# DM1092_Power_Supply.net
KiCad netlist of a schematic drawn in Altium Designer
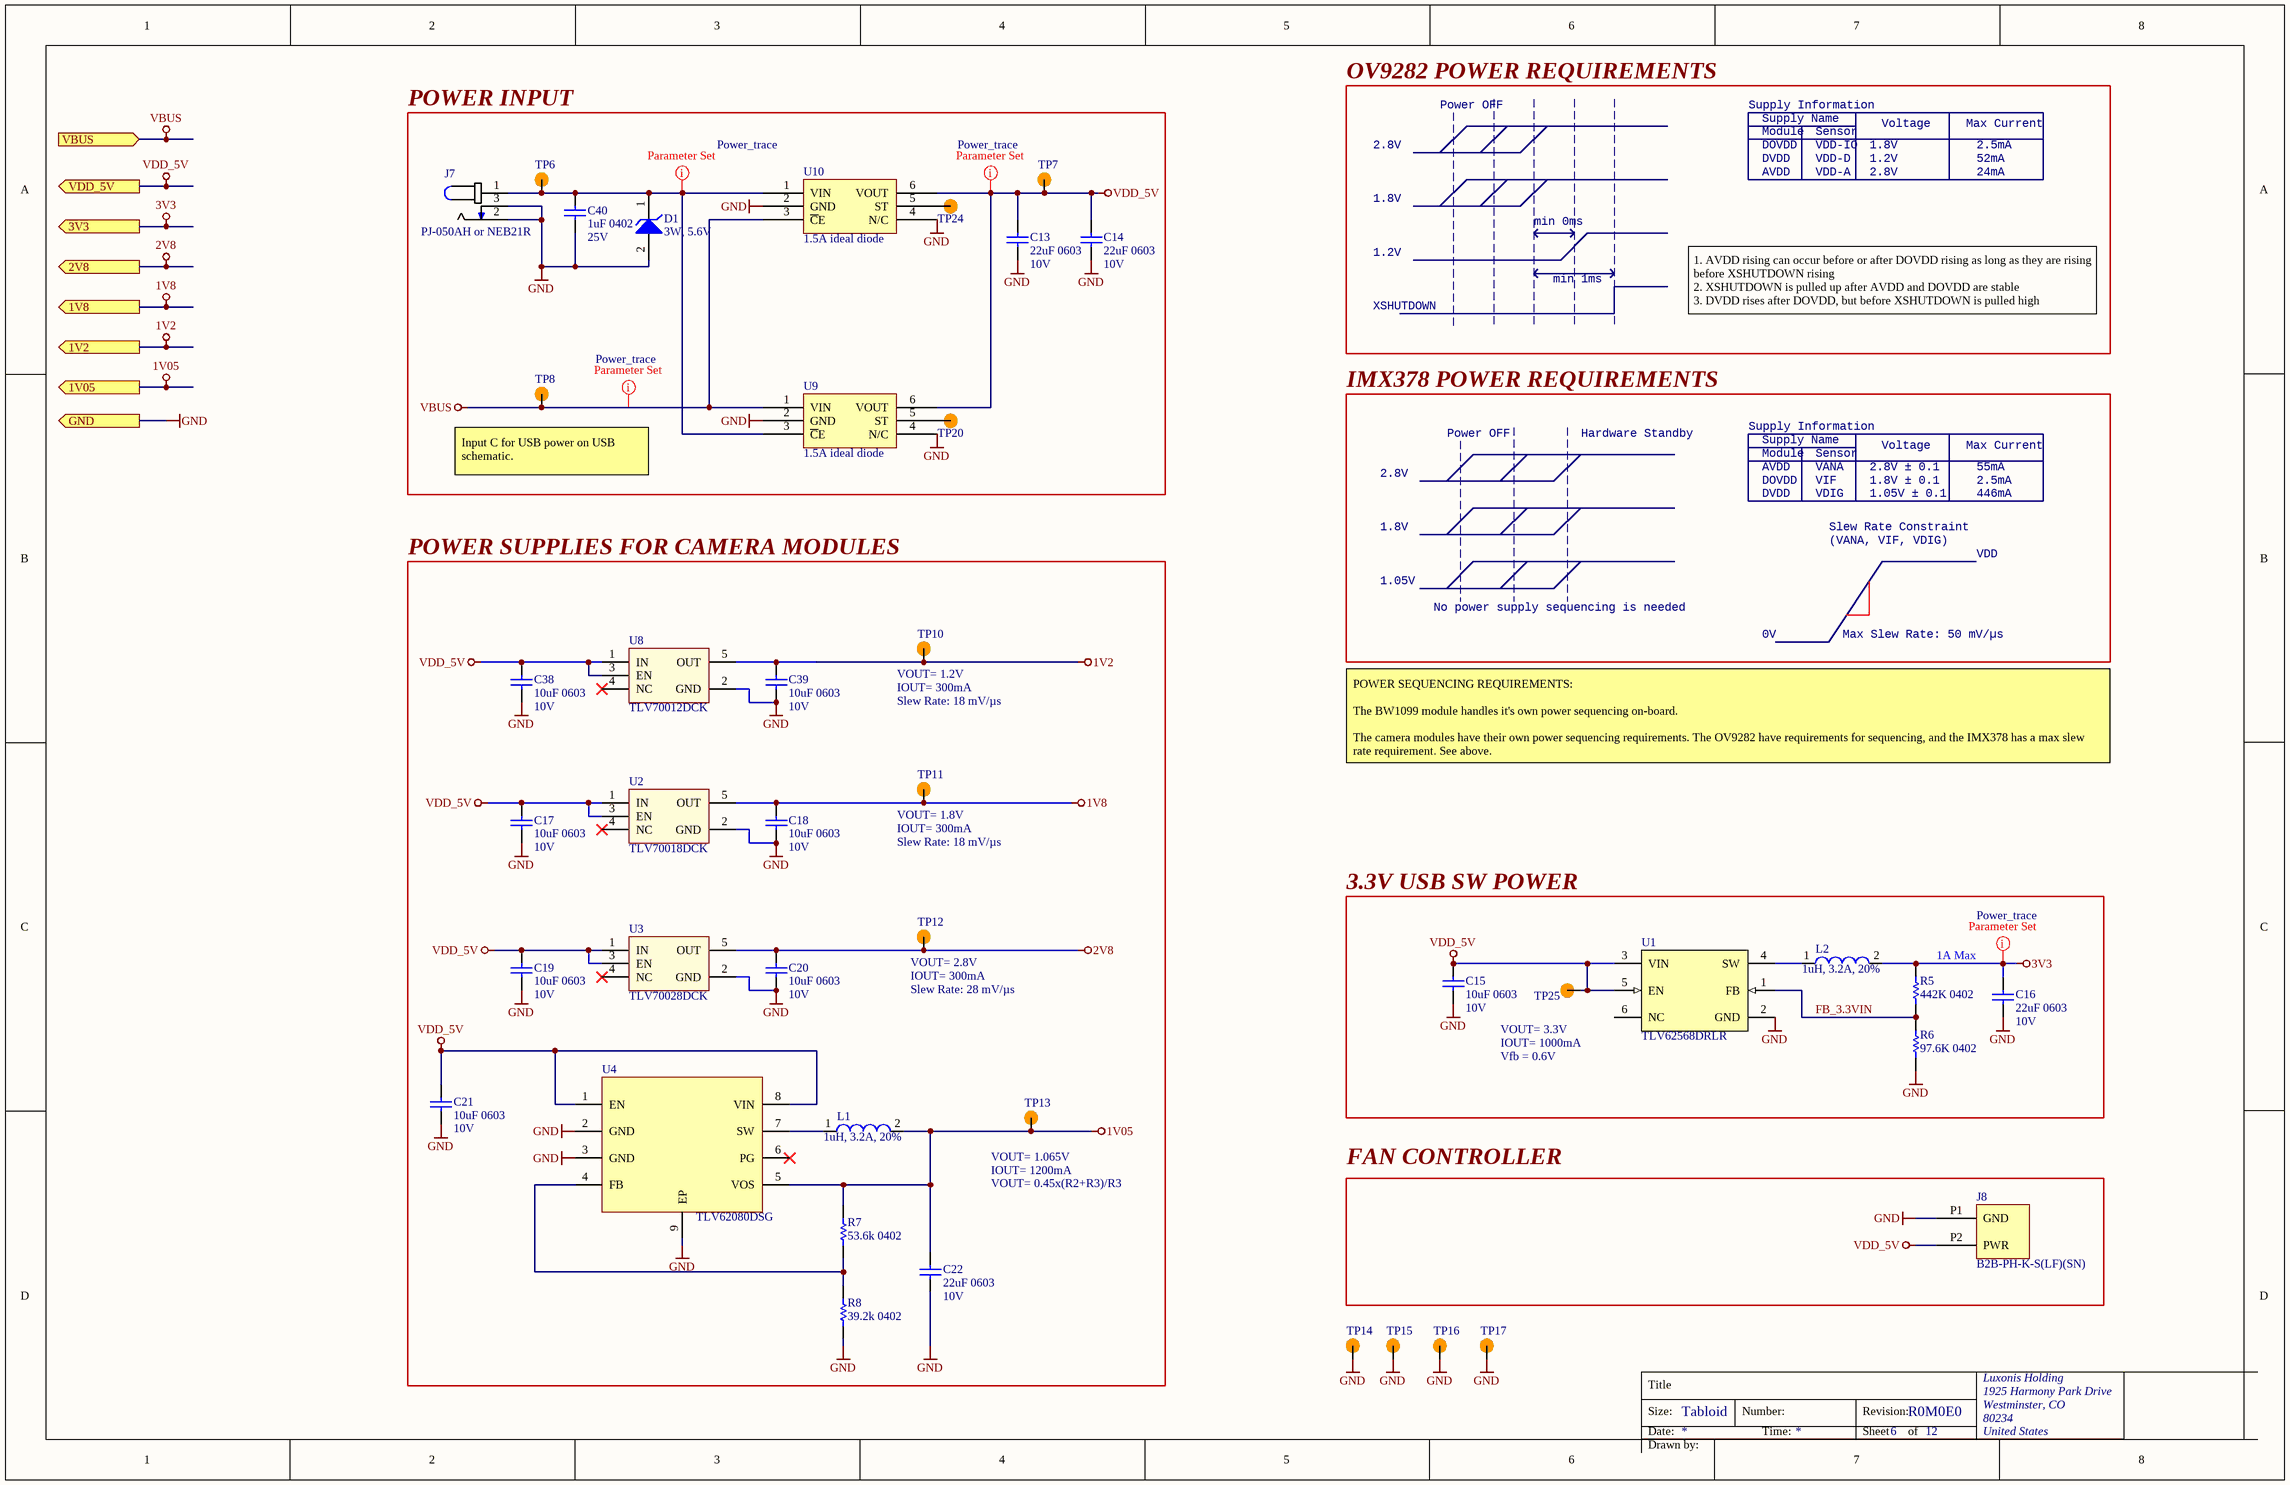
[diagram p0: DM1092_Power_Supply.SchDoc]

(export (version "E")
  (design (tool "Eeschema 10.0.6"))
  (components
    (comp (ref "C13")
      (value "22uF 0603")
      (footprint "CAP_Altium_Vault_Generic:CAPC0603(1608)100_L")
      (description "CAP CER 22UF 10V X5R 0603 20%")
      (fields (field (name "TOLERANCE") "20%") (field (name "VOLTAGE RATING") "10V"))
      (libsource (lib "LuxonisMaster") (part "GRM188R61A226ME15D"))
    )
    (comp (ref "C14")
      (value "22uF 0603")
      (footprint "CAP_Altium_Vault_Generic:CAPC0603(1608)100_L")
      (description "CAP CER 22UF 10V X5R 0603 20%")
      (fields (field (name "TOLERANCE") "20%") (field (name "VOLTAGE RATING") "10V"))
      (libsource (lib "LuxonisMaster") (part "GRM188R61A226ME15D"))
    )
    (comp (ref "C15")
      (value "10uF 0603")
      (footprint "CAP_Altium_Vault_Generic:CAPC0603(1608)100_L")
      (description "CAP CER 10UF 10V X5R 0603 20%")
      (fields (field (name "TOLERANCE") "20%") (field (name "VOLTAGE RATING") "10V"))
      (libsource (lib "LuxonisMaster") (part "GRM188R61A106ME69D"))
    )
    (comp (ref "C16")
      (value "22uF 0603")
      (footprint "CAP_Altium_Vault_Generic:CAPC0603(1608)100_N")
      (description "CAP CER 22UF 10V X5R 0603 20%")
      (fields (field (name "TOLERANCE") "20%") (field (name "VOLTAGE RATING") "10V"))
      (libsource (lib "LuxonisMaster") (part "GRM188R61A226ME15D"))
    )
    (comp (ref "C17")
      (value "10uF 0603")
      (footprint "CAP_Altium_Vault_Generic:CAPC0603(1608)100_L")
      (description "CAP CER 10UF 10V X5R 0603 20%")
      (fields (field (name "TOLERANCE") "20%") (field (name "VOLTAGE RATING") "10V"))
      (libsource (lib "LuxonisMaster") (part "GRM188R61A106ME69D"))
    )
    (comp (ref "C18")
      (value "10uF 0603")
      (footprint "CAP_Altium_Vault_Generic:CAPC0603(1608)100_L")
      (description "CAP CER 10UF 10V X5R 0603 20%")
      (fields (field (name "TOLERANCE") "20%") (field (name "VOLTAGE RATING") "10V"))
      (libsource (lib "LuxonisMaster") (part "GRM188R61A106ME69D"))
    )
    (comp (ref "C19")
      (value "10uF 0603")
      (footprint "CAP_Altium_Vault_Generic:CAPC0603(1608)100_L")
      (description "CAP CER 10UF 10V X5R 0603 20%")
      (fields (field (name "TOLERANCE") "20%") (field (name "VOLTAGE RATING") "10V"))
      (libsource (lib "LuxonisMaster") (part "GRM188R61A106ME69D"))
    )
    (comp (ref "C20")
      (value "10uF 0603")
      (footprint "CAP_Altium_Vault_Generic:CAPC0603(1608)100_L")
      (description "CAP CER 10UF 10V X5R 0603 20%")
      (fields (field (name "TOLERANCE") "20%") (field (name "VOLTAGE RATING") "10V"))
      (libsource (lib "LuxonisMaster") (part "GRM188R61A106ME69D"))
    )
    (comp (ref "C21")
      (value "10uF 0603")
      (footprint "CAP_Altium_Vault_Generic:CAPC0603(1608)100_L")
      (description "CAP CER 10UF 10V X5R 0603 20%")
      (fields (field (name "TOLERANCE") "20%") (field (name "VOLTAGE RATING") "10V"))
      (libsource (lib "LuxonisMaster") (part "GRM188R61A106ME69D"))
    )
    (comp (ref "C22")
      (value "22uF 0603")
      (footprint "CAP_Altium_Vault_Generic:CAPC0603(1608)100_L")
      (description "CAP CER 22UF 10V X5R 0603 20%")
      (fields (field (name "TOLERANCE") "20%") (field (name "VOLTAGE RATING") "10V"))
      (libsource (lib "LuxonisMaster") (part "GRM188R61A226ME15D"))
    )
    (comp (ref "C38")
      (value "10uF 0603")
      (footprint "CAP_Altium_Vault_Generic:CAPC0603(1608)100_L")
      (description "CAP CER 10UF 10V X5R 0603 20%")
      (fields (field (name "TOLERANCE") "20%") (field (name "VOLTAGE RATING") "10V"))
      (libsource (lib "LuxonisMaster") (part "GRM188R61A106ME69D"))
    )
    (comp (ref "C39")
      (value "10uF 0603")
      (footprint "CAP_Altium_Vault_Generic:CAPC0603(1608)100_L")
      (description "CAP CER 10UF 10V X5R 0603 20%")
      (fields (field (name "TOLERANCE") "20%") (field (name "VOLTAGE RATING") "10V"))
      (libsource (lib "LuxonisMaster") (part "GRM188R61A106ME69D"))
    )
    (comp (ref "C40")
      (value "1uF 0402")
      (footprint "CAP_Altium_Vault_Generic:CAPC0402(1005)70_L")
      (description "CAP CER 1UF 25V X5R 0402 10%")
      (fields
        (field (name "TOLERANCE") "10%")
        (field (name "VOLTAGE") "25V")
        (field (name "VOLTAGE RATING") "25V")
      )
      (libsource (lib "LuxonisMaster") (part "GRM155R61E105KA12D"))
    )
    (comp (ref "D1")
      (value "3W, 5.6V")
      (footprint "DM1092_R0M0E0:1SMB5919BT3G")
      (description "DIODE ZENER 5.6V 3W SMB")
      (fields (field (name "TOLERANCE") "5%"))
      (libsource (lib "DM1092_R0M0E0") (part "1SMB5919BT3G"))
    )
    (comp (ref "J7")
      (value "PJ-050AH or NEB21R")
      (footprint "LuxonisMaster:PJ-050AH/NEB21R_COMBO")
      (description "CONN POWER PIN 2 POS RA PTH Barrel jack 2.1mm x 5.5mm combo footprint")
      (libsource (lib "LuxonisMaster") (part "PJ-050AH/NEB21R_COMBO"))
    )
    (comp (ref "J8")
      (value "B2B-PH-K-S(LF)(SN)")
      (footprint "LuxonisMaster:B2B-PH-K-S(LF)(SN)")
      (description "CONN HEADER VERT 2POS 2MM")
      (fields (field (name "MANUFACTURER") "JST"))
      (libsource (lib "LuxonisMaster") (part "B2B-PH-K-S(LF)(SN)"))
    )
    (comp (ref "L1")
      (value "1uH, 3.2A, 20%")
      (footprint "LuxonisMaster:DFE252012P-1R0M=P2")
      (description "FIXED IND 1UH 3.2A 42 MOHM SMD")
      (fields
        (field (name "MANUFACTURER") "Murata")
        (field (name "MANUFACTURER PART NUMBER") "DFE252012P-1R0M=P2")
      )
      (libsource (lib "LuxonisMaster") (part "DFE252012P-1R0M=P2"))
    )
    (comp (ref "L2")
      (value "1uH, 3.2A, 20%")
      (footprint "LuxonisMaster:DFE252012P-1R0M=P2")
      (description "FIXED IND 1UH 3.2A 42 MOHM SMD")
      (fields
        (field (name "MANUFACTURER") "Murata")
        (field (name "MANUFACTURER PART NUMBER") "DFE252012P-1R0M=P2")
      )
      (libsource (lib "LuxonisMaster") (part "DFE252012P-1R0M=P2"))
    )
    (comp (ref "R5")
      (value "442K 0402")
      (footprint "RES_Altium_Vault_Generic:RESC0402(1005)_N")
      (description "RES SMD 442K OHM 1% 1/16W 0402")
      (fields (field (name "TOLERANCE") "1%"))
      (libsource (lib "DM1092_R0M0E0") (part "CRCW0402442KFKED"))
    )
    (comp (ref "R6")
      (value "97.6K 0402")
      (footprint "RES_Altium_Vault_Generic:RESC0402(1005)_N")
      (description "RES SMD 97.6K OHM 1% 1/16W 0402")
      (fields (field (name "TOLERANCE") "1%"))
      (libsource (lib "DM1092_R0M0E0") (part "CRCW040297K6FKED"))
    )
    (comp (ref "R7")
      (value "53.6k 0402")
      (footprint "RES_Altium_Vault_Generic:RESC0402(1005)_L")
      (description "RES SMD 53.6K OHM 1% 1/16W 0402")
      (fields (field (name "TOLERANCE") "1%"))
      (libsource (lib "LuxonisMaster") (part "CRCW040253K6FKED"))
    )
    (comp (ref "R8")
      (value "39.2k 0402")
      (footprint "RES_Altium_Vault_Generic:RESC0402(1005)_L")
      (description "RES SMD 39.2K OHM 1% 1/16W 0402")
      (fields (field (name "TOLERANCE") "1%"))
      (libsource (lib "LuxonisMaster") (part "CRCW040239K2FKED"))
    )
    (comp (ref "TP6")
      (value "TP100_200_NS")
      (footprint "LuxonisMaster:TP100_200_NS")
      (libsource (lib "LuxonisMaster") (part "TEST_POINT"))
    )
    (comp (ref "TP7")
      (value "TP100_200_NS")
      (footprint "LuxonisMaster:TP100_200_NS")
      (libsource (lib "LuxonisMaster") (part "TEST_POINT"))
    )
    (comp (ref "TP8")
      (value "TP100_200_NS")
      (footprint "LuxonisMaster:TP100_200_NS")
      (libsource (lib "LuxonisMaster") (part "TEST_POINT"))
    )
    (comp (ref "TP10")
      (value "TP100_200_NS")
      (footprint "LuxonisMaster:TP100_200_NS")
      (libsource (lib "LuxonisMaster") (part "TEST_POINT"))
    )
    (comp (ref "TP11")
      (value "TP100_200_NS")
      (footprint "LuxonisMaster:TP100_200_NS")
      (libsource (lib "LuxonisMaster") (part "TEST_POINT"))
    )
    (comp (ref "TP12")
      (value "TP100_200_NS")
      (footprint "LuxonisMaster:TP100_200_NS")
      (libsource (lib "LuxonisMaster") (part "TEST_POINT"))
    )
    (comp (ref "TP13")
      (value "TP100_200_NS")
      (footprint "LuxonisMaster:TP100_200_NS")
      (libsource (lib "LuxonisMaster") (part "TEST_POINT"))
    )
    (comp (ref "TP14")
      (value "TP100_200_NS")
      (footprint "LuxonisMaster:TP100_200_NS")
      (libsource (lib "LuxonisMaster") (part "TEST_POINT"))
    )
    (comp (ref "TP15")
      (value "TP100_200_NS")
      (footprint "LuxonisMaster:TP100_200_NS")
      (libsource (lib "LuxonisMaster") (part "TEST_POINT"))
    )
    (comp (ref "TP16")
      (value "TP100_200_NS")
      (footprint "LuxonisMaster:TP100_200_NS")
      (libsource (lib "LuxonisMaster") (part "TEST_POINT"))
    )
    (comp (ref "TP17")
      (value "TP100_200_NS")
      (footprint "LuxonisMaster:TP100_200_NS")
      (libsource (lib "LuxonisMaster") (part "TEST_POINT"))
    )
    (comp (ref "TP20")
      (value "TP100_200_NS")
      (footprint "LuxonisMaster:TP100_200_NS")
      (libsource (lib "LuxonisMaster") (part "TEST_POINT"))
    )
    (comp (ref "TP24")
      (value "TP100_200_NS")
      (footprint "LuxonisMaster:TP100_200_NS")
      (libsource (lib "LuxonisMaster") (part "TEST_POINT"))
    )
    (comp (ref "TP25")
      (value "TP100_200_NS")
      (footprint "LuxonisMaster:TP100_200_NS")
      (libsource (lib "LuxonisMaster") (part "TEST_POINT"))
    )
    (comp (ref "U1")
      (value "TLV62568DRLR")
      (footprint "BW1092_R0M0E0:TLV62568DRLR")
      (description "IC REG BUCK ADJ 1A SOT563-6")
      (libsource (lib "DM1092_R0M0E0") (part "TLV62568DRLR"))
    )
    (comp (ref "U2")
      (value "TLV70018DCK")
      (footprint "LuxonisMaster:TLV70018DCK")
      (description "IC REG LINEAR 1.8V 200MA SC70-5 Linear Voltage Regulator IC  1 Output  200mA SC-70-5")
      (libsource (lib "LuxonisMaster") (part "TLV70018DCK"))
    )
    (comp (ref "U3")
      (value "TLV70028DCK")
      (footprint "LuxonisMaster:TLV70028DCK")
      (description "IC REG LINEAR 2.8V 200MA SC70-5 Linear Voltage Regulator IC  1 Output  200mA SC-70-5")
      (libsource (lib "LuxonisMaster") (part "TLV70028DCK"))
    )
    (comp (ref "U4")
      (value "TLV62080DSG")
      (footprint "LuxonisMaster:TLV62080DSG")
      (description "IC REG BUCK ADJ 1.2A SYNC 8WSON")
      (libsource (lib "LuxonisMaster") (part "TLV62080DSG"))
    )
    (comp (ref "U8")
      (value "TLV70012DCK")
      (footprint "LuxonisMaster:TLV70012DCK")
      (description "IC REG LINEAR 1.2V 200MA SC70-5")
      (libsource (lib "LuxonisMaster") (part "TLV70012DCK"))
    )
    (comp (ref "U9")
      (value "1.5A ideal diode")
      (footprint "BW1098OBC_R2M0E2:LM66100DCKR")
      (description "IC OR CTRLR IDEAL DIODE SC70-6")
      (libsource (lib "BW1098OBC_R2M0E2") (part "LM66100DCKR"))
    )
    (comp (ref "U10")
      (value "1.5A ideal diode")
      (footprint "BW1098OBC_R2M0E2:LM66100DCKR")
      (description "IC OR CTRLR IDEAL DIODE SC70-6")
      (libsource (lib "BW1098OBC_R2M0E2") (part "LM66100DCKR"))
    )
  )
  (nets
    (net (code "1") (name "/FB_3.3VIN") (class "Default")
      (node (ref "R5") (pin "1") (pinfunction "1_1") (pintype "passive"))
      (node (ref "R6") (pin "2") (pinfunction "2_2") (pintype "passive"))
      (node (ref "U1") (pin "1") (pinfunction "FB_1") (pintype "input"))
    )
    (net (code "2") (name "1V2") (class "Default")
      (node (ref "C39") (pin "2") (pinfunction "2_2") (pintype "passive"))
      (node (ref "TP10") (pin "1") (pintype "passive"))
      (node (ref "U8") (pin "5") (pinfunction "OUT_5") (pintype "passive"))
    )
    (net (code "3") (name "1V05") (class "Default")
      (node (ref "C22") (pin "2") (pinfunction "2_2") (pintype "passive"))
      (node (ref "L1") (pin "2") (pinfunction "2_2") (pintype "passive"))
      (node (ref "R7") (pin "2") (pinfunction "2_2") (pintype "passive"))
      (node (ref "TP13") (pin "1") (pintype "passive"))
      (node (ref "U4") (pin "5") (pinfunction "VOS_5") (pintype "passive"))
    )
    (net (code "4") (name "1V8") (class "Default")
      (node (ref "C18") (pin "2") (pinfunction "2_2") (pintype "passive"))
      (node (ref "TP11") (pin "1") (pintype "passive"))
      (node (ref "U2") (pin "5") (pinfunction "OUT_5") (pintype "passive"))
    )
    (net (code "5") (name "2V8") (class "Default")
      (node (ref "C20") (pin "2") (pinfunction "2_2") (pintype "passive"))
      (node (ref "TP12") (pin "1") (pintype "passive"))
      (node (ref "U3") (pin "5") (pinfunction "OUT_5") (pintype "passive"))
    )
    (net (code "6") (name "3V3") (class "Default")
      (node (ref "C16") (pin "1") (pinfunction "1_1") (pintype "passive"))
      (node (ref "L2") (pin "2") (pinfunction "2_2") (pintype "passive"))
      (node (ref "R5") (pin "2") (pinfunction "2_2") (pintype "passive"))
    )
    (net (code "7") (name "GND") (class "Default")
      (node (ref "C13") (pin "1") (pinfunction "1_1") (pintype "passive"))
      (node (ref "C14") (pin "1") (pinfunction "1_1") (pintype "passive"))
      (node (ref "C15") (pin "1") (pinfunction "1_1") (pintype "passive"))
      (node (ref "C16") (pin "2") (pinfunction "2_2") (pintype "passive"))
      (node (ref "C17") (pin "1") (pinfunction "1_1") (pintype "passive"))
      (node (ref "C18") (pin "1") (pinfunction "1_1") (pintype "passive"))
      (node (ref "C19") (pin "1") (pinfunction "1_1") (pintype "passive"))
      (node (ref "C20") (pin "1") (pinfunction "1_1") (pintype "passive"))
      (node (ref "C21") (pin "1") (pinfunction "1_1") (pintype "passive"))
      (node (ref "C22") (pin "1") (pinfunction "1_1") (pintype "passive"))
      (node (ref "C38") (pin "1") (pinfunction "1_1") (pintype "passive"))
      (node (ref "C39") (pin "1") (pinfunction "1_1") (pintype "passive"))
      (node (ref "C40") (pin "1") (pinfunction "1_1") (pintype "passive"))
      (node (ref "D1") (pin "2") (pinfunction "A_2") (pintype "passive"))
      (node (ref "J7") (pin "2") (pinfunction "2_2") (pintype "passive"))
      (node (ref "J7") (pin "3") (pinfunction "3_3") (pintype "passive"))
      (node (ref "J8") (pin "P1") (pinfunction "GND_P1") (pintype "passive"))
      (node (ref "R6") (pin "1") (pinfunction "1_1") (pintype "passive"))
      (node (ref "R8") (pin "1") (pinfunction "1_1") (pintype "passive"))
      (node (ref "TP14") (pin "1") (pintype "passive"))
      (node (ref "TP15") (pin "1") (pintype "passive"))
      (node (ref "TP16") (pin "1") (pintype "passive"))
      (node (ref "TP17") (pin "1") (pintype "passive"))
      (node (ref "U1") (pin "2") (pinfunction "GND_2") (pintype "power_in"))
      (node (ref "U10") (pin "2") (pinfunction "GND_2") (pintype "passive"))
      (node (ref "U10") (pin "4") (pinfunction "N/C_4") (pintype "passive"))
      (node (ref "U2") (pin "2") (pinfunction "GND_2") (pintype "passive"))
      (node (ref "U3") (pin "2") (pinfunction "GND_2") (pintype "passive"))
      (node (ref "U4") (pin "2") (pinfunction "GND_2") (pintype "passive"))
      (node (ref "U4") (pin "3") (pinfunction "GND_3") (pintype "passive"))
      (node (ref "U4") (pin "9") (pinfunction "EP_9") (pintype "passive"))
      (node (ref "U8") (pin "2") (pinfunction "GND_2") (pintype "passive"))
      (node (ref "U9") (pin "2") (pinfunction "GND_2") (pintype "passive"))
      (node (ref "U9") (pin "4") (pinfunction "N/C_4") (pintype "passive"))
    )
    (net (code "8") (name "Net-(D1-K)") (class "Default")
      (node (ref "C40") (pin "2") (pinfunction "2_2") (pintype "passive"))
      (node (ref "D1") (pin "1") (pinfunction "K_1") (pintype "passive"))
      (node (ref "J7") (pin "1") (pinfunction "1_1") (pintype "passive"))
      (node (ref "TP6") (pin "1") (pintype "passive"))
      (node (ref "U10") (pin "1") (pinfunction "VIN_1") (pintype "passive"))
      (node (ref "U9") (pin "3") (pinfunction "~{C}E_3") (pintype "passive"))
    )
    (net (code "9") (name "Net-(U1-SW)") (class "Default")
      (node (ref "L2") (pin "1") (pinfunction "1_1") (pintype "passive"))
      (node (ref "U1") (pin "4") (pinfunction "SW_4") (pintype "power_in"))
    )
    (net (code "10") (name "Net-(U4-FB)") (class "Default")
      (node (ref "R7") (pin "1") (pinfunction "1_1") (pintype "passive"))
      (node (ref "R8") (pin "2") (pinfunction "2_2") (pintype "passive"))
      (node (ref "U4") (pin "4") (pinfunction "FB_4") (pintype "passive"))
    )
    (net (code "11") (name "Net-(U4-SW)") (class "Default")
      (node (ref "L1") (pin "1") (pinfunction "1_1") (pintype "passive"))
      (node (ref "U4") (pin "7") (pinfunction "SW_7") (pintype "passive"))
    )
    (net (code "12") (name "Net-(U9-ST)") (class "Default")
      (node (ref "TP20") (pin "1") (pintype "passive"))
      (node (ref "U9") (pin "5") (pinfunction "ST_5") (pintype "passive"))
    )
    (net (code "13") (name "Net-(U10-ST)") (class "Default")
      (node (ref "TP24") (pin "1") (pintype "passive"))
      (node (ref "U10") (pin "5") (pinfunction "ST_5") (pintype "passive"))
    )
    (net (code "14") (name "VBUS") (class "Default")
      (node (ref "TP8") (pin "1") (pintype "passive"))
      (node (ref "U10") (pin "3") (pinfunction "~{C}E_3") (pintype "passive"))
      (node (ref "U9") (pin "1") (pinfunction "VIN_1") (pintype "passive"))
    )
    (net (code "15") (name "VDD_5V") (class "Default")
      (node (ref "C13") (pin "2") (pinfunction "2_2") (pintype "passive"))
      (node (ref "C14") (pin "2") (pinfunction "2_2") (pintype "passive"))
      (node (ref "C15") (pin "2") (pinfunction "2_2") (pintype "passive"))
      (node (ref "C17") (pin "2") (pinfunction "2_2") (pintype "passive"))
      (node (ref "C19") (pin "2") (pinfunction "2_2") (pintype "passive"))
      (node (ref "C21") (pin "2") (pinfunction "2_2") (pintype "passive"))
      (node (ref "C38") (pin "2") (pinfunction "2_2") (pintype "passive"))
      (node (ref "J8") (pin "P2") (pinfunction "PWR_P2") (pintype "passive"))
      (node (ref "TP25") (pin "1") (pintype "passive"))
      (node (ref "TP7") (pin "1") (pintype "passive"))
      (node (ref "U1") (pin "3") (pinfunction "VIN_3") (pintype "power_in"))
      (node (ref "U1") (pin "5") (pinfunction "EN_5") (pintype "input"))
      (node (ref "U10") (pin "6") (pinfunction "VOUT_6") (pintype "passive"))
      (node (ref "U2") (pin "1") (pinfunction "IN_1") (pintype "passive"))
      (node (ref "U2") (pin "3") (pinfunction "EN_3") (pintype "passive"))
      (node (ref "U3") (pin "1") (pinfunction "IN_1") (pintype "passive"))
      (node (ref "U3") (pin "3") (pinfunction "EN_3") (pintype "passive"))
      (node (ref "U4") (pin "1") (pinfunction "EN_1") (pintype "passive"))
      (node (ref "U4") (pin "8") (pinfunction "VIN_8") (pintype "passive"))
      (node (ref "U8") (pin "1") (pinfunction "IN_1") (pintype "passive"))
      (node (ref "U8") (pin "3") (pinfunction "EN_3") (pintype "passive"))
      (node (ref "U9") (pin "6") (pinfunction "VOUT_6") (pintype "passive"))
    )
    (net (code "16") (name "unconnected-(U1-NC-Pad6)") (class "Default")
      (node (ref "U1") (pin "6") (pinfunction "NC_6") (pintype "passive"))
    )
    (net (code "17") (name "unconnected-(U2-NC-Pad4)") (class "Default")
      (node (ref "U2") (pin "4") (pinfunction "NC_4") (pintype "passive+no_connect"))
    )
    (net (code "18") (name "unconnected-(U3-NC-Pad4)") (class "Default")
      (node (ref "U3") (pin "4") (pinfunction "NC_4") (pintype "passive+no_connect"))
    )
    (net (code "19") (name "unconnected-(U4-PG-Pad6)") (class "Default")
      (node (ref "U4") (pin "6") (pinfunction "PG_6") (pintype "passive+no_connect"))
    )
    (net (code "20") (name "unconnected-(U8-NC-Pad4)") (class "Default")
      (node (ref "U8") (pin "4") (pinfunction "NC_4") (pintype "passive+no_connect"))
    )
  )
)
